# 02.net
KiCad netlist of a schematic drawn in Altium Designer
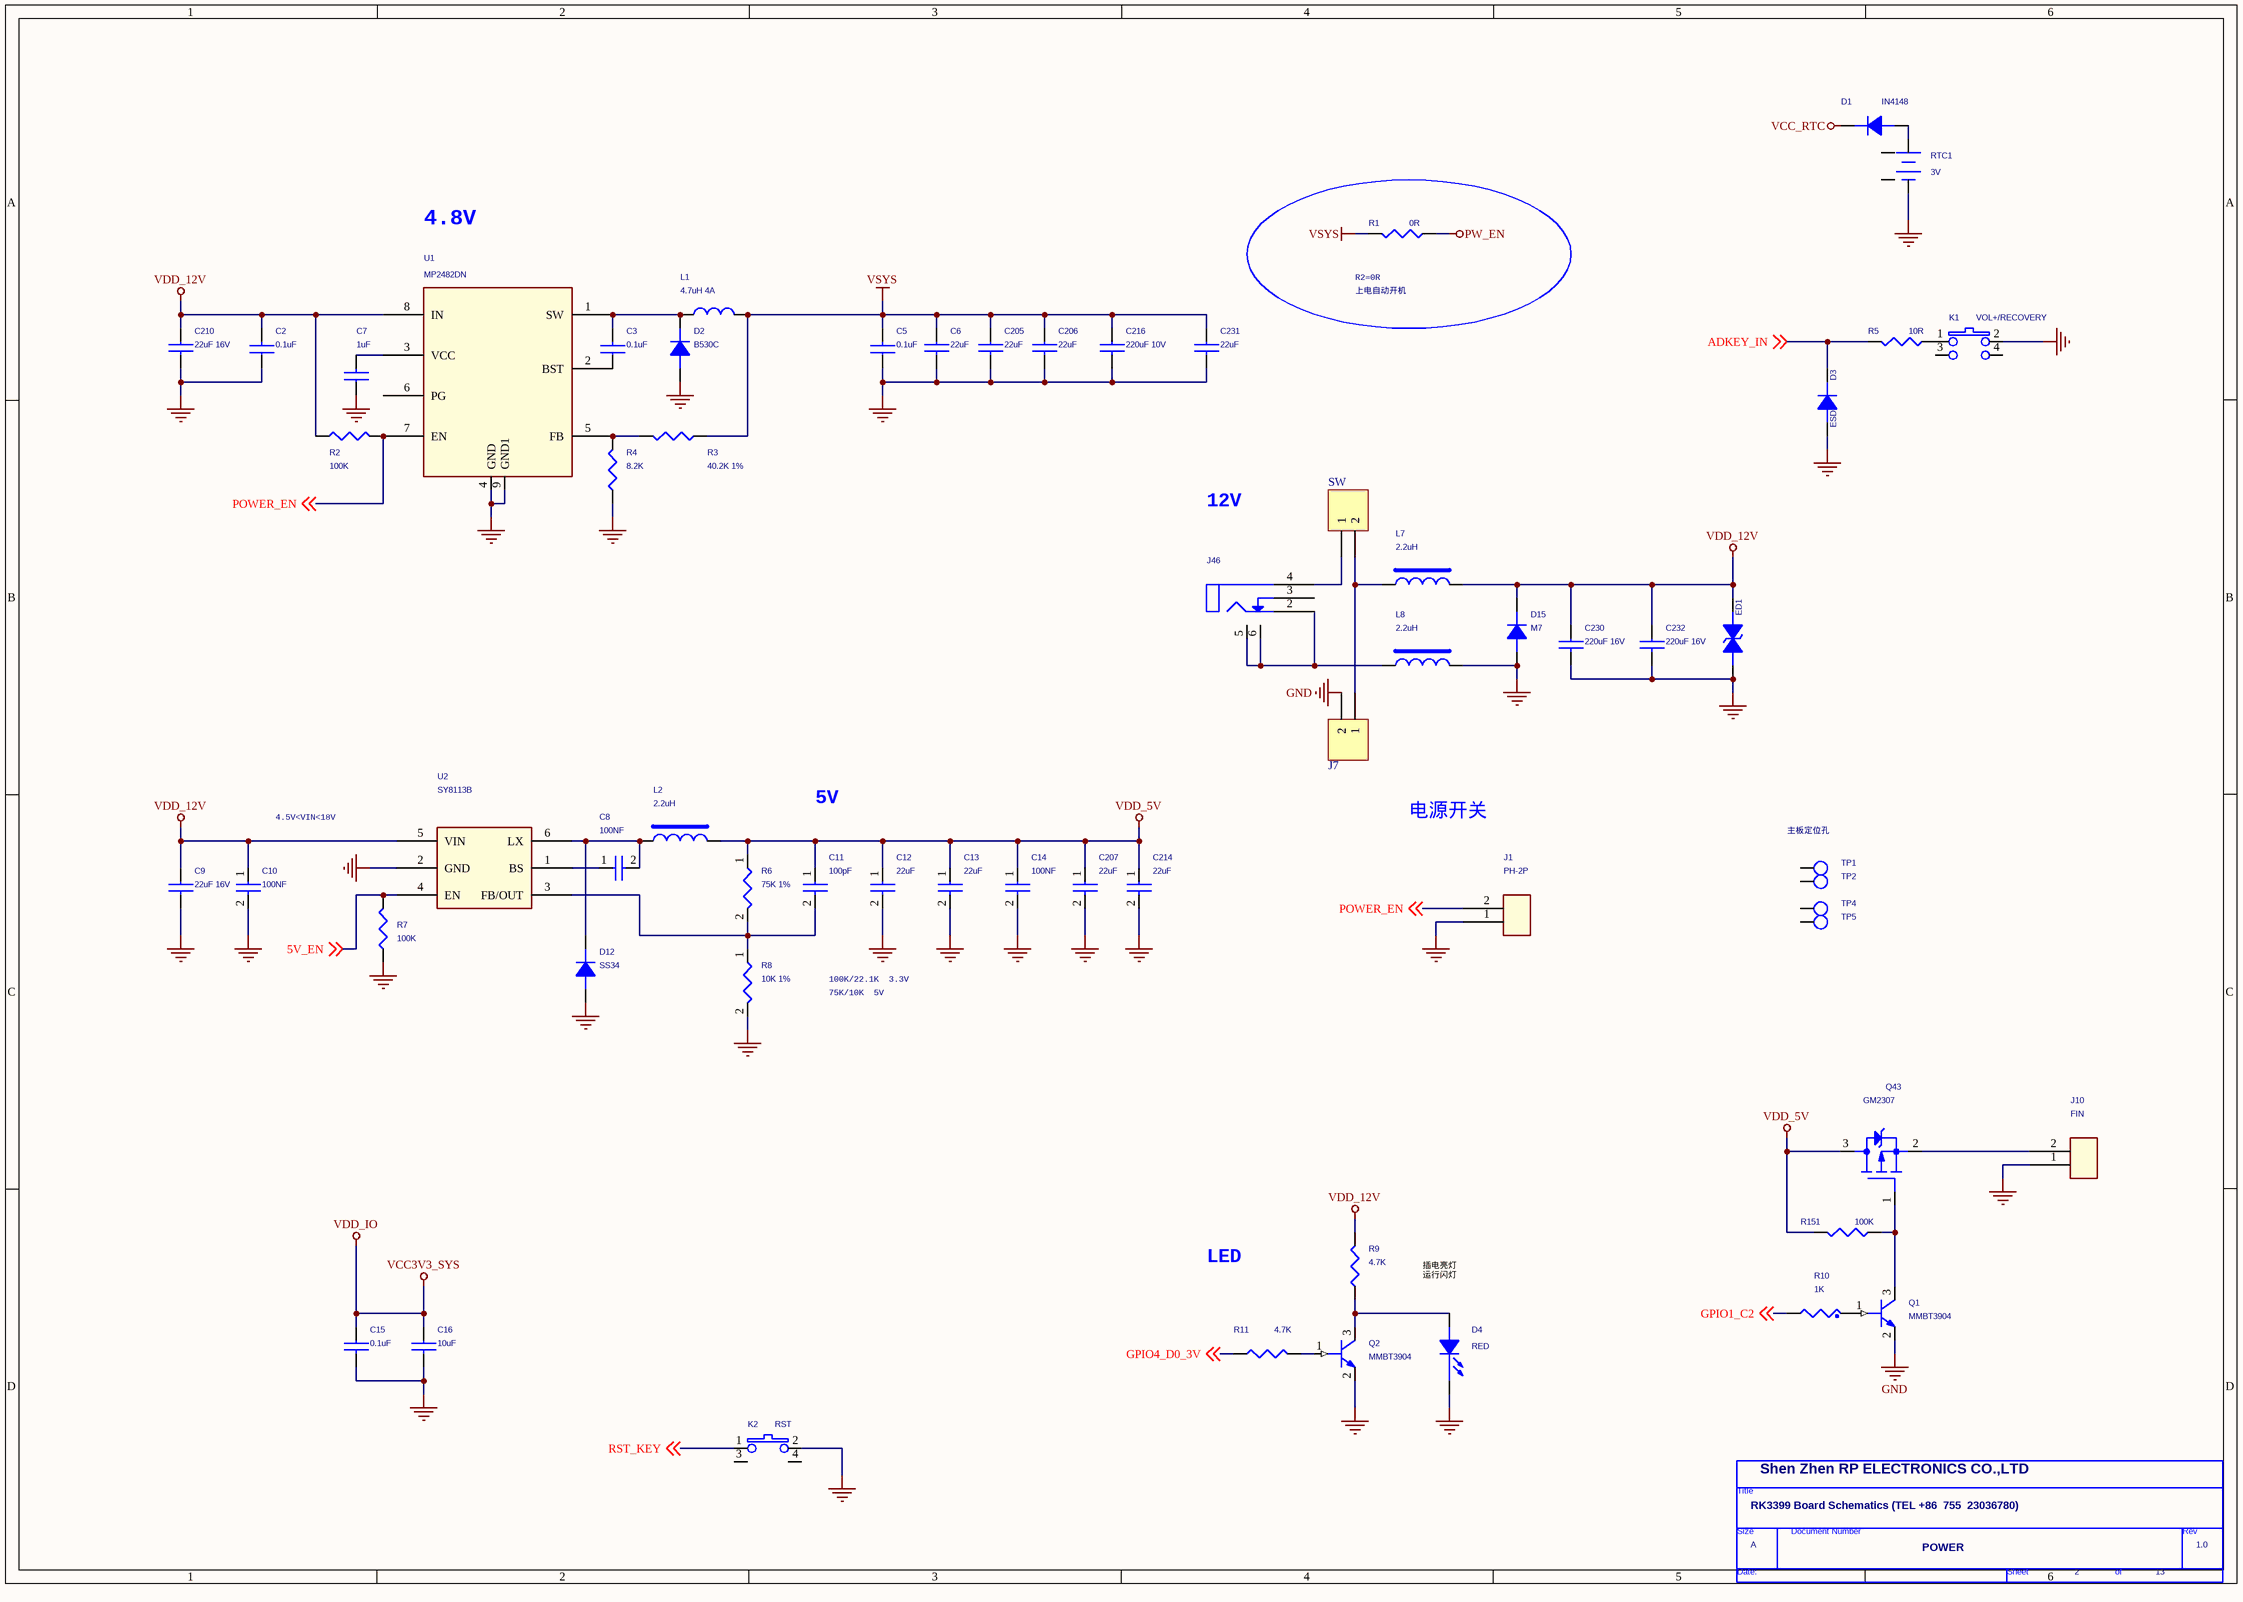
[diagram p0: 02.SchDoc]

(export (version "E")
  (design (tool "Eeschema 10.0.6"))
  (components
    (comp (ref "C2") (value "0.1uF") (footprint "0805c") (libsource (lib "*") (part "C1005_0")))
    (comp (ref "C3") (value "0.1uF") (footprint "0805C") (libsource (lib "*") (part "C1005_0")))
    (comp (ref "C5") (value "0.1uF") (footprint "0805C") (libsource (lib "*") (part "C1005_0")))
    (comp (ref "C6")
      (value "22uF")
      (footprint "0805C")
      (description "CAP,MLCC,100nF,+/-10%,X7R,6.3V,SMD0402")
      (libsource (lib "*") (part "CAP NP_3"))
    )
    (comp (ref "C7") (value "1uF") (footprint "0805C") (libsource (lib "*") (part "C1005_0")))
    (comp (ref "C8")
      (value "100NF")
      (description "cap,100.00nF,+/-10%,25V,X5R,C0402")
      (fields
        (field (name "VOLTAGE") "25V")
        (field (name "MANUFACTURER") "TDK")
        (field (name "CREATED BY") "JJJ")
      )
      (libsource (lib "*") (part "CAP NP_Dup2"))
    )
    (comp (ref "C9") (value "22uF 16V") (libsource (lib "*") (part "CAP NP_Dup8")))
    (comp (ref "C10")
      (value "100NF")
      (description "cap,100.00nF,+/-10%,25V,X5R,C0402")
      (fields
        (field (name "VOLTAGE") "25V")
        (field (name "TOLERANCE") "10%")
        (field (name "CREATED BY") "JJJ")
      )
      (libsource (lib "*") (part "CAP NP_Dup2"))
    )
    (comp (ref "C11")
      (value "100pF")
      (description "cap,100.00pF,+/-5%,50V,C0G,C0402")
      (fields
        (field (name "VOLTAGE") "50V")
        (field (name "TOLERANCE") "5%")
        (field (name "CREATED BY") "JJJ")
      )
      (libsource (lib "*") (part "CAP NP_Dup2"))
    )
    (comp (ref "C12")
      (value "22uF")
      (footprint "0805C")
      (description "cap,22.00uF,+/-10%,10V,X5R,C0805")
      (fields
        (field (name "VOLTAGE") "10V")
        (field (name "TOLERANCE") "10%")
        (field (name "CREATED BY") "JJJ")
      )
      (libsource (lib "*") (part "CAP NP_Dup2"))
    )
    (comp (ref "C13")
      (value "22uF")
      (footprint "0805C")
      (description "cap,10.00uF,+/-10%,10V,X5R,C0805")
      (fields
        (field (name "VOLTAGE") "10V")
        (field (name "TOLERANCE") "10%")
        (field (name "CREATED BY") "JJJ")
      )
      (libsource (lib "*") (part "CAP NP_Dup2"))
    )
    (comp (ref "C14")
      (value "100NF")
      (description "cap,100.00nF,+/-10%,16V,X5R,C0402")
      (fields
        (field (name "VOLTAGE") "16V")
        (field (name "TOLERANCE") "10%")
        (field (name "CREATED BY") "JJJ")
      )
      (libsource (lib "*") (part "CAP NP_Dup2"))
    )
    (comp (ref "C15") (value "0.1uF") (footprint "0805C") (libsource (lib "*") (part "02CAPP")))
    (comp (ref "C16")
      (value "10uF")
      (footprint "0805C")
      (description "CAP,MLCC,100nF,+/-10%,X7R,6.3V,SMD0402")
      (libsource (lib "*") (part "CAP NP_3"))
    )
    (comp (ref "C205")
      (value "22uF")
      (footprint "0805C")
      (description "CAP,MLCC,100nF,+/-10%,X7R,6.3V,SMD0402")
      (libsource (lib "*") (part "CAP NP_3"))
    )
    (comp (ref "C206")
      (value "22uF")
      (footprint "0805C")
      (description "CAP,MLCC,100nF,+/-10%,X7R,6.3V,SMD0402")
      (libsource (lib "*") (part "CAP NP_3"))
    )
    (comp (ref "C207")
      (value "22uF")
      (footprint "0805C")
      (description "cap,22.00uF,+/-10%,10V,X5R,C0805")
      (fields
        (field (name "VOLTAGE") "10V")
        (field (name "TOLERANCE") "10%")
        (field (name "CREATED BY") "JJJ")
      )
      (libsource (lib "*") (part "CAP NP_Dup2"))
    )
    (comp (ref "C210") (value "22uF 16V") (libsource (lib "*") (part "CAP NP_Dup8")))
    (comp (ref "C214")
      (value "22uF")
      (footprint "0805C")
      (description "cap,22.00uF,+/-10%,10V,X5R,C0805")
      (fields
        (field (name "VOLTAGE") "10V")
        (field (name "TOLERANCE") "10%")
        (field (name "CREATED BY") "JJJ")
      )
      (libsource (lib "*") (part "CAP NP_Dup2"))
    )
    (comp (ref "C216") (value "220uF 10V") (libsource (lib "*") (part "CAP NP_Dup8")))
    (comp (ref "C230") (value "220uF 16V") (libsource (lib "*") (part "CAP NP_Dup8")))
    (comp (ref "C231")
      (value "22uF")
      (footprint "0805C")
      (description "CAP,MLCC,100nF,+/-10%,X7R,6.3V,SMD0402")
      (libsource (lib "*") (part "CAP NP_3"))
    )
    (comp (ref "C232") (value "220uF 16V") (libsource (lib "*") (part "CAP NP_Dup8")))
    (comp (ref "D1") (value "IN4148") (libsource (lib "*") (part "DIODE_Dup2")))
    (comp (ref "D2") (value "B530C") (libsource (lib "*") (part "DIODE_Dup1")))
    (comp (ref "D3") (value "ESD") (libsource (lib "*") (part "DIODE_Dup2")))
    (comp (ref "D4") (value "RED") (libsource (lib "*") (part "LED")))
    (comp (ref "D12") (value "SS34") (libsource (lib "*") (part "DIODE_Dup1")))
    (comp (ref "D15") (value "M7") (libsource (lib "*") (part "DIODE_Dup1")))
    (comp (ref "ED1") (value "ESD") (libsource (lib "*") (part "DIODE BI-DIR TRIG")))
    (comp (ref "J1") (value "PH-2P") (libsource (lib "*") (part "CON2")))
    (comp (ref "J7")
      (value "Header 2")
      (footprint "VH3.96*2")
      (description "Header, 2-Pin")
      (fields (field (name "PUBLISHER") "Altium Limited"))
      (libsource (lib "") (part "Header 2_1"))
    )
    (comp (ref "J10") (value "FIN") (libsource (lib "*") (part "CON4_0_Dup1")))
    (comp (ref "J46") (value "DC_5V") (libsource (lib "*") (part "CONN JACK PWR_0_Dup1")))
    (comp (ref "K1") (value "VOL+/RECOVERY") (footprint "KEYB") (libsource (lib "*") (part "KEYB_0")))
    (comp (ref "K2") (value "RST") (footprint "KEYB") (libsource (lib "*") (part "KEYB_1")))
    (comp (ref "L1") (value "4.7uH 4A") (footprint "VLS252012E") (libsource (lib "*") (part "VLS252012E_0")))
    (comp (ref "L2")
      (value "2.2uH")
      (description "Power Inductor,3.3uH,0.2,IND_404030")
      (fields
        (field (name "TOLERANCE") "20%")
        (field (name "MANUFACTURER") "sunlord")
        (field (name "CREATED BY") "YTL")
      )
      (libsource (lib "*") (part "INDUCTORS OF FERRITE"))
    )
    (comp (ref "L7")
      (value "2.2uH")
      (description "Power Inductor,3.3uH,0.2,IND_404030")
      (fields
        (field (name "TOLERANCE") "20%")
        (field (name "MANUFACTURER") "sunlord")
        (field (name "CREATED BY") "YTL")
      )
      (libsource (lib "*") (part "INDUCTORS OF FERRITE"))
    )
    (comp (ref "L8")
      (value "2.2uH")
      (description "Power Inductor,3.3uH,0.2,IND_404030")
      (fields
        (field (name "MANUFACTURER") "sunlord")
        (field (name "TOLERANCE") "20%")
        (field (name "CREATED BY") "YTL")
      )
      (libsource (lib "*") (part "INDUCTORS OF FERRITE"))
    )
    (comp (ref "Q1") (value "MMBT3904") (libsource (lib "*") (part "NPN_1")))
    (comp (ref "Q2") (value "MMBT3904") (libsource (lib "*") (part "NPN_1")))
    (comp (ref "Q43") (value "GM2307") (libsource (lib "*") (part "APM2301")))
    (comp (ref "R1") (value "0R") (libsource (lib "*") (part "R_Dup1")))
    (comp (ref "R2")
      (value "100K")
      (footprint "0805")
      (description "通用厚膜电阻,10K,+/-5%,R0402,1/16W.")
      (fields
        (field (name "TOLERANCE") "5%")
        (field (name "MANUFACTURER") "YAGEO")
        (field (name "CREATED BY") "YTL")
      )
      (libsource (lib "*") (part "RESISTOR_5"))
    )
    (comp (ref "R3") (value "40.2K 1%") (footprint "0805") (libsource (lib "*") (part "R1005_0_Dup1")))
    (comp (ref "R4") (value "8.2K") (libsource (lib "*") (part "R1005_0_Dup1")))
    (comp (ref "R5")
      (value "10R")
      (description "ROHS CHIP RES 4.7Ohm 1/8W +/-5%")
      (libsource (lib "*") (part "RES 1B"))
    )
    (comp (ref "R6")
      (value "75K 1%")
      (footprint "0805")
      (description "通用厚膜电阻,75K,+/-1%,R0402,1/16W.")
      (fields
        (field (name "TOLERANCE") "1%")
        (field (name "MANUFACTURER") "YAGEO")
        (field (name "CREATED BY") "YTL")
      )
      (libsource (lib "*") (part "RESISTOR_Dup1"))
    )
    (comp (ref "R7") (value "100K") (libsource (lib "*") (part "R_Dup1")))
    (comp (ref "R8")
      (value "10K 1%")
      (footprint "0805")
      (description "通用厚膜电阻,10K,+/-1%,R0402,1/16W.")
      (fields
        (field (name "TOLERANCE") "1%")
        (field (name "MANUFACTURER") "YAGEO")
        (field (name "CREATED BY") "YTL")
      )
      (libsource (lib "*") (part "RESISTOR_Dup1"))
    )
    (comp (ref "R9") (value "4.7K") (footprint "0805") (libsource (lib "*") (part "R1005_0_Dup1")))
    (comp (ref "R10")
      (value "1K")
      (description "RES MF 10.0K 1/16W 1% 0402")
      (fields (field (name "TOLERANCE") "1%"))
      (libsource (lib "*") (part "RES"))
    )
    (comp (ref "R11") (value "4.7K") (libsource (lib "*") (part "R_Dup1")))
    (comp (ref "R151") (value "100K") (footprint "0805") (libsource (lib "*") (part "R1005_0_Dup1")))
    (comp (ref "RTC1") (value "3V") (libsource (lib "*") (part "BATTERY_5")))
    (comp (ref "SW")
      (value "Header 2")
      (footprint "VH3.96*2")
      (description "Header, 2-Pin")
      (fields (field (name "PUBLISHER") "Altium Limited"))
      (libsource (lib "Miscellaneous Connectors") (part "Header 2"))
    )
    (comp (ref "TP1") (value "T POINT R") (libsource (lib "*") (part "T POINT R")))
    (comp (ref "TP2") (value "T POINT R") (libsource (lib "*") (part "T POINT R")))
    (comp (ref "TP4") (value "T POINT R") (libsource (lib "*") (part "T POINT R")))
    (comp (ref "TP5") (value "T POINT R") (libsource (lib "*") (part "T POINT R")))
    (comp (ref "U1") (value "MP2482DN") (libsource (lib "*") (part "MP2482DN_1")))
    (comp (ref "U2")
      (value "SY8113B")
      (fields (field (name "MANUFACTURER") "Silergy（矽力杰）") (field (name "CREATED BY") "JJJ"))
      (libsource (lib "*") (part "DCDC_SY8113"))
    )
  )
  (nets
    (net (code "1") (name "5V_EN") (class "Default")
      (node (ref "R7") (pin "2") (pinfunction "2_2") (pintype "passive"))
      (node (ref "U2") (pin "4") (pinfunction "EN_4") (pintype "passive"))
    )
    (net (code "2") (name "ADKEY_IN") (class "Default")
      (node (ref "D3") (pin "2") (pinfunction "K_2") (pintype "passive"))
      (node (ref "R5") (pin "1") (pinfunction "1_1") (pintype "passive"))
    )
    (net (code "3") (name "GND") (class "Default")
      (node (ref "C10") (pin "2") (pinfunction "2_2") (pintype "passive"))
      (node (ref "C12") (pin "2") (pinfunction "2_2") (pintype "passive"))
      (node (ref "C13") (pin "2") (pinfunction "2_2") (pintype "passive"))
      (node (ref "C14") (pin "2") (pinfunction "2_2") (pintype "passive"))
      (node (ref "C15") (pin "2") (pinfunction "2_2") (pintype "passive"))
      (node (ref "C16") (pin "2") (pinfunction "2_2") (pintype "passive"))
      (node (ref "C2") (pin "1") (pinfunction "1_1") (pintype "passive"))
      (node (ref "C205") (pin "2") (pinfunction "2_2") (pintype "passive"))
      (node (ref "C206") (pin "2") (pinfunction "2_2") (pintype "passive"))
      (node (ref "C207") (pin "2") (pinfunction "2_2") (pintype "passive"))
      (node (ref "C210") (pin "2") (pinfunction "2_2") (pintype "passive"))
      (node (ref "C214") (pin "2") (pinfunction "2_2") (pintype "passive"))
      (node (ref "C216") (pin "2") (pinfunction "2_2") (pintype "passive"))
      (node (ref "C230") (pin "2") (pinfunction "2_2") (pintype "passive"))
      (node (ref "C231") (pin "2") (pinfunction "2_2") (pintype "passive"))
      (node (ref "C232") (pin "2") (pinfunction "2_2") (pintype "passive"))
      (node (ref "C5") (pin "1") (pinfunction "1_1") (pintype "passive"))
      (node (ref "C6") (pin "2") (pinfunction "2_2") (pintype "passive"))
      (node (ref "C7") (pin "1") (pinfunction "1_1") (pintype "passive"))
      (node (ref "C9") (pin "2") (pinfunction "2_2") (pintype "passive"))
      (node (ref "D12") (pin "1") (pinfunction "A_1") (pintype "passive"))
      (node (ref "D15") (pin "1") (pinfunction "A_1") (pintype "passive"))
      (node (ref "D2") (pin "1") (pinfunction "A_1") (pintype "passive"))
      (node (ref "D3") (pin "1") (pinfunction "A_1") (pintype "passive"))
      (node (ref "D4") (pin "2") (pinfunction "CATHODE_2") (pintype "passive"))
      (node (ref "ED1") (pin "2") (pinfunction "K_2") (pintype "passive"))
      (node (ref "J1") (pin "1") (pinfunction "1_1") (pintype "passive"))
      (node (ref "J10") (pin "1") (pinfunction "1_1") (pintype "passive"))
      (node (ref "J7") (pin "2") (pinfunction "2_2") (pintype "passive"))
      (node (ref "K1") (pin "2") (pinfunction "2_2") (pintype "passive"))
      (node (ref "K2") (pin "2") (pinfunction "2_2") (pintype "passive"))
      (node (ref "L8") (pin "2") (pinfunction "2_2") (pintype "passive"))
      (node (ref "Q1") (pin "2") (pinfunction "EMITTER_2") (pintype "passive"))
      (node (ref "Q2") (pin "2") (pinfunction "EMITTER_2") (pintype "passive"))
      (node (ref "R4") (pin "2") (pinfunction "2_2") (pintype "passive"))
      (node (ref "R7") (pin "1") (pinfunction "1_1") (pintype "passive"))
      (node (ref "R8") (pin "2") (pinfunction "2_2") (pintype "passive"))
      (node (ref "RTC1") (pin "2") (pinfunction "-_2") (pintype "passive"))
      (node (ref "U1") (pin "4") (pinfunction "GND_4") (pintype "passive"))
      (node (ref "U1") (pin "9") (pinfunction "GND1_9") (pintype "passive"))
      (node (ref "U2") (pin "2") (pinfunction "GND_2") (pintype "passive"))
    )
    (net (code "4") (name "GPIO1_C2") (class "Default")
      (node (ref "R10") (pin "2") (pinfunction "2_2") (pintype "passive"))
    )
    (net (code "5") (name "GPIO4_D0_3V") (class "Default")
      (node (ref "R11") (pin "1") (pinfunction "1_1") (pintype "passive"))
    )
    (net (code "6") (name "Net-(D1-A)") (class "Default")
      (node (ref "D1") (pin "1") (pinfunction "A_1") (pintype "passive"))
      (node (ref "RTC1") (pin "1") (pinfunction "+_1") (pintype "passive"))
    )
    (net (code "7") (name "Net-(D2-K)") (class "Default")
      (node (ref "C3") (pin "2") (pinfunction "2_2") (pintype "passive"))
      (node (ref "D2") (pin "2") (pinfunction "K_2") (pintype "passive"))
      (node (ref "L1") (pin "1") (pinfunction "1_1") (pintype "passive"))
      (node (ref "U1") (pin "1") (pinfunction "SW_1") (pintype "passive"))
    )
    (net (code "8") (name "Net-(D4-ANODE)") (class "Default")
      (node (ref "D4") (pin "1") (pinfunction "ANODE_1") (pintype "passive"))
      (node (ref "Q2") (pin "3") (pinfunction "COLLECT_3") (pintype "passive"))
      (node (ref "R9") (pin "2") (pinfunction "2_2") (pintype "passive"))
    )
    (net (code "9") (name "Net-(D12-K)") (class "Default")
      (node (ref "C8") (pin "2") (pinfunction "2_2") (pintype "passive"))
      (node (ref "D12") (pin "2") (pinfunction "K_2") (pintype "passive"))
      (node (ref "L2") (pin "1") (pinfunction "1_1") (pintype "passive"))
      (node (ref "U2") (pin "6") (pinfunction "LX_6") (pintype "passive"))
    )
    (net (code "10") (name "Net-(J7-Pad1)") (class "Default")
      (node (ref "J7") (pin "1") (pinfunction "1_1") (pintype "passive"))
      (node (ref "L7") (pin "1") (pinfunction "1_1") (pintype "passive"))
      (node (ref "SW") (pin "2") (pinfunction "2_2") (pintype "passive"))
    )
    (net (code "11") (name "Net-(J46-Pad2)") (class "Default")
      (node (ref "J46") (pin "2") (pinfunction "2_2") (pintype "passive"))
      (node (ref "J46") (pin "5") (pinfunction "5_5") (pintype "passive"))
      (node (ref "J46") (pin "6") (pinfunction "6_6") (pintype "passive"))
      (node (ref "L8") (pin "1") (pinfunction "1_1") (pintype "passive"))
    )
    (net (code "12") (name "Net-(J46-Pad4)") (class "Default")
      (node (ref "J46") (pin "4") (pinfunction "4_4") (pintype "passive"))
      (node (ref "SW") (pin "1") (pinfunction "1_1") (pintype "passive"))
    )
    (net (code "13") (name "Net-(K1-Pad1)") (class "Default")
      (node (ref "K1") (pin "1") (pinfunction "1_1") (pintype "passive"))
      (node (ref "R5") (pin "2") (pinfunction "2_2") (pintype "passive"))
    )
    (net (code "14") (name "Net-(Q1-BASE)") (class "Default")
      (node (ref "Q1") (pin "1") (pinfunction "BASE_1") (pintype "input"))
      (node (ref "R10") (pin "1") (pinfunction "1_1") (pintype "passive"))
    )
    (net (code "15") (name "Net-(Q1-COLLECT)") (class "Default")
      (node (ref "Q1") (pin "3") (pinfunction "COLLECT_3") (pintype "passive"))
      (node (ref "Q43") (pin "1") (pinfunction "G_1") (pintype "passive"))
      (node (ref "R151") (pin "2") (pinfunction "2_2") (pintype "passive"))
    )
    (net (code "16") (name "Net-(Q2-BASE)") (class "Default")
      (node (ref "Q2") (pin "1") (pinfunction "BASE_1") (pintype "input"))
      (node (ref "R11") (pin "2") (pinfunction "2_2") (pintype "passive"))
    )
    (net (code "17") (name "Net-(Q43-S)") (class "Default")
      (node (ref "J10") (pin "2") (pinfunction "2_2") (pintype "passive"))
      (node (ref "Q43") (pin "2") (pinfunction "S_2") (pintype "passive"))
    )
    (net (code "18") (name "Net-(U1-BST)") (class "Default")
      (node (ref "C3") (pin "1") (pinfunction "1_1") (pintype "passive"))
      (node (ref "U1") (pin "2") (pinfunction "BST_2") (pintype "passive"))
    )
    (net (code "19") (name "Net-(U1-FB)") (class "Default")
      (node (ref "R3") (pin "1") (pinfunction "1_1") (pintype "passive"))
      (node (ref "R4") (pin "1") (pinfunction "1_1") (pintype "passive"))
      (node (ref "U1") (pin "5") (pinfunction "FB_5") (pintype "passive"))
    )
    (net (code "20") (name "Net-(U1-VCC)") (class "Default")
      (node (ref "C7") (pin "2") (pinfunction "2_2") (pintype "passive"))
      (node (ref "U1") (pin "3") (pinfunction "VCC_3") (pintype "passive"))
    )
    (net (code "21") (name "Net-(U2-BS)") (class "Default")
      (node (ref "C8") (pin "1") (pinfunction "1_1") (pintype "passive"))
      (node (ref "U2") (pin "1") (pinfunction "BS_1") (pintype "passive"))
    )
    (net (code "22") (name "Net-(U2-FB{slash}OUT)") (class "Default")
      (node (ref "C11") (pin "2") (pinfunction "2_2") (pintype "passive"))
      (node (ref "R6") (pin "2") (pinfunction "2_2") (pintype "passive"))
      (node (ref "R8") (pin "1") (pinfunction "1_1") (pintype "passive"))
      (node (ref "U2") (pin "3") (pinfunction "FB/OUT_3") (pintype "passive"))
    )
    (net (code "23") (name "POWER_EN") (class "Default")
      (node (ref "J1") (pin "2") (pinfunction "2_2") (pintype "passive"))
      (node (ref "R2") (pin "2") (pinfunction "2_2") (pintype "passive"))
      (node (ref "U1") (pin "7") (pinfunction "EN_7") (pintype "passive"))
    )
    (net (code "24") (name "PW_EN") (class "Default")
      (node (ref "R1") (pin "1") (pinfunction "1_1") (pintype "passive"))
    )
    (net (code "25") (name "RST_KEY") (class "Default")
      (node (ref "K2") (pin "1") (pinfunction "1_1") (pintype "passive"))
    )
    (net (code "26") (name "VCC3V3_SYS") (class "Default")
      (node (ref "C15") (pin "1") (pinfunction "1_1") (pintype "passive"))
      (node (ref "C16") (pin "1") (pinfunction "1_1") (pintype "passive"))
    )
    (net (code "27") (name "VCC_RTC") (class "Default")
      (node (ref "D1") (pin "2") (pinfunction "K_2") (pintype "passive"))
    )
    (net (code "28") (name "VDD_5V") (class "Default")
      (node (ref "C11") (pin "1") (pinfunction "1_1") (pintype "passive"))
      (node (ref "C12") (pin "1") (pinfunction "1_1") (pintype "passive"))
      (node (ref "C13") (pin "1") (pinfunction "1_1") (pintype "passive"))
      (node (ref "C14") (pin "1") (pinfunction "1_1") (pintype "passive"))
      (node (ref "C207") (pin "1") (pinfunction "1_1") (pintype "passive"))
      (node (ref "C214") (pin "1") (pinfunction "1_1") (pintype "passive"))
      (node (ref "L2") (pin "2") (pinfunction "2_2") (pintype "passive"))
      (node (ref "Q43") (pin "3") (pinfunction "D_3") (pintype "passive"))
      (node (ref "R151") (pin "1") (pinfunction "1_1") (pintype "passive"))
      (node (ref "R6") (pin "1") (pinfunction "1_1") (pintype "passive"))
    )
    (net (code "29") (name "VDD_12V") (class "Default")
      (node (ref "C10") (pin "1") (pinfunction "1_1") (pintype "passive"))
      (node (ref "C2") (pin "2") (pinfunction "2_2") (pintype "passive"))
      (node (ref "C210") (pin "1") (pinfunction "1_1") (pintype "passive"))
      (node (ref "C230") (pin "1") (pinfunction "1_1") (pintype "passive"))
      (node (ref "C232") (pin "1") (pinfunction "1_1") (pintype "passive"))
      (node (ref "C9") (pin "1") (pinfunction "1_1") (pintype "passive"))
      (node (ref "D15") (pin "2") (pinfunction "K_2") (pintype "passive"))
      (node (ref "ED1") (pin "1") (pinfunction "A_1") (pintype "passive"))
      (node (ref "L7") (pin "2") (pinfunction "2_2") (pintype "passive"))
      (node (ref "R2") (pin "1") (pinfunction "1_1") (pintype "passive"))
      (node (ref "R9") (pin "1") (pinfunction "1_1") (pintype "passive"))
      (node (ref "U1") (pin "8") (pinfunction "IN_8") (pintype "passive"))
      (node (ref "U2") (pin "5") (pinfunction "VIN_5") (pintype "passive"))
    )
    (net (code "30") (name "VSYS") (class "Default")
      (node (ref "C205") (pin "1") (pinfunction "1_1") (pintype "passive"))
      (node (ref "C206") (pin "1") (pinfunction "1_1") (pintype "passive"))
      (node (ref "C216") (pin "1") (pinfunction "1_1") (pintype "passive"))
      (node (ref "C231") (pin "1") (pinfunction "1_1") (pintype "passive"))
      (node (ref "C5") (pin "2") (pinfunction "2_2") (pintype "passive"))
      (node (ref "C6") (pin "1") (pinfunction "1_1") (pintype "passive"))
      (node (ref "L1") (pin "2") (pinfunction "2_2") (pintype "passive"))
      (node (ref "R1") (pin "2") (pinfunction "2_2") (pintype "passive"))
      (node (ref "R3") (pin "2") (pinfunction "2_2") (pintype "passive"))
    )
    (net (code "31") (name "unconnected-(J46-Pad3)") (class "Default")
      (node (ref "J46") (pin "3") (pinfunction "3_3") (pintype "passive"))
    )
    (net (code "32") (name "unconnected-(K1-Pad3)") (class "Default")
      (node (ref "K1") (pin "3") (pinfunction "3_3") (pintype "passive"))
    )
    (net (code "33") (name "unconnected-(K1-Pad4)") (class "Default")
      (node (ref "K1") (pin "4") (pinfunction "4_4") (pintype "passive"))
    )
    (net (code "34") (name "unconnected-(K2-Pad3)") (class "Default")
      (node (ref "K2") (pin "3") (pinfunction "3_3") (pintype "passive"))
    )
    (net (code "35") (name "unconnected-(K2-Pad4)") (class "Default")
      (node (ref "K2") (pin "4") (pinfunction "4_4") (pintype "passive"))
    )
    (net (code "36") (name "unconnected-(RTC1-Pad3)") (class "Default")
      (node (ref "RTC1") (pin "3") (pinfunction "3_3") (pintype "passive"))
    )
    (net (code "37") (name "unconnected-(RTC1-Pad4)") (class "Default")
      (node (ref "RTC1") (pin "4") (pinfunction "4_4") (pintype "passive"))
    )
    (net (code "38") (name "unconnected-(TP1-TP-Pad1)") (class "Default")
      (node (ref "TP1") (pin "1") (pinfunction "TP_1") (pintype "passive"))
    )
    (net (code "39") (name "unconnected-(TP2-TP-Pad1)") (class "Default")
      (node (ref "TP2") (pin "1") (pinfunction "TP_1") (pintype "passive"))
    )
    (net (code "40") (name "unconnected-(TP4-TP-Pad1)") (class "Default")
      (node (ref "TP4") (pin "1") (pinfunction "TP_1") (pintype "passive"))
    )
    (net (code "41") (name "unconnected-(TP5-TP-Pad1)") (class "Default")
      (node (ref "TP5") (pin "1") (pinfunction "TP_1") (pintype "passive"))
    )
    (net (code "42") (name "unconnected-(U1-PG-Pad6)") (class "Default")
      (node (ref "U1") (pin "6") (pinfunction "PG_6") (pintype "passive"))
    )
  )
)
